# HeadSensors.net
KiCad netlist of a schematic drawn in Altium Designer
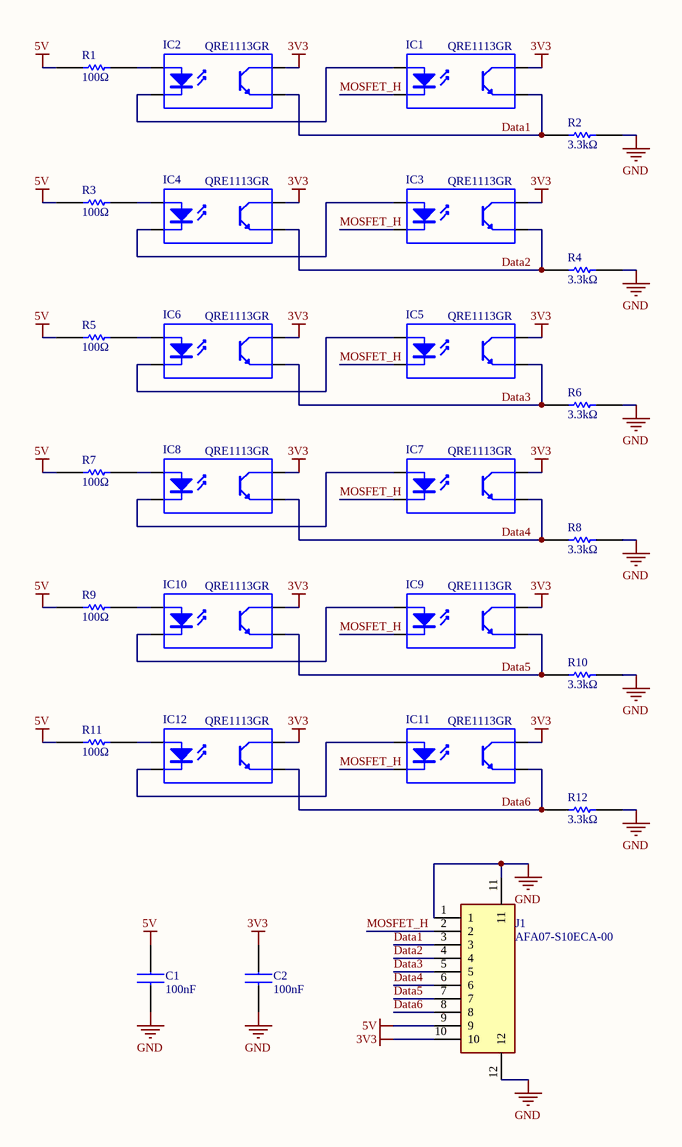
[diagram p0: HeadSensors.SchDoc]

(export (version "E")
  (design (tool "Eeschema 10.0.6"))
  (components
    (comp (ref "C1")
      (value "100nF")
      (footprint "CAP0805")
      (description "Multilayer Ceramic Capacitors MLCC - SMD/SMT 50 V 0.1uF X7R 0805 10%")
      (fields (field (name "MANUFACTURER_PART_NUMBER") "CC0805KRX7R9BB104"))
      (libsource (lib "StandartComponents") (part "CC0805KRX7R9BB104"))
    )
    (comp (ref "C2")
      (value "100nF")
      (footprint "CAP0805")
      (description "Multilayer Ceramic Capacitors MLCC - SMD/SMT 50 V 0.1uF X7R 0805 10%")
      (fields (field (name "MANUFACTURER_PART_NUMBER") "CC0805KRX7R9BB104"))
      (libsource (lib "StandartComponents") (part "CC0805KRX7R9BB104"))
    )
    (comp (ref "IC1")
      (value "QRE1113GR")
      (footprint "SOIC4- Head")
      (description "IC IR-SENSOR")
      (fields
        (field (name "MANUFACTURER") "ON Semiconductor")
        (field (name "LIBRARY CONTROL - PERSON THAT CHECKED FOOTPRINT") "Lucas")
        (field (name "LIBRARY CONTROL - PERSON THAT CHECKED SCHEMATIC") "Lucas")
        (field (name "LIBRARY CONTROL - PERSON THAT DID THE LAST UPDATE FOOTPRINT") "Mateus(Dimas)")
        (field (name "LIBRARY CONTROL - PERSON THAT DID THE LAST UPDATE SCHEMATIC") "Mateus(Dimas)")
      )
      (libsource (lib "MainComponents") (part "QRE1113GR_H"))
    )
    (comp (ref "IC2")
      (value "QRE1113GR")
      (footprint "SOIC4- Head")
      (description "IC IR-SENSOR")
      (fields
        (field (name "MANUFACTURER") "ON Semiconductor")
        (field (name "LIBRARY CONTROL - PERSON THAT CHECKED FOOTPRINT") "Lucas")
        (field (name "LIBRARY CONTROL - PERSON THAT CHECKED SCHEMATIC") "Lucas")
        (field (name "LIBRARY CONTROL - PERSON THAT DID THE LAST UPDATE FOOTPRINT") "Mateus(Dimas)")
        (field (name "LIBRARY CONTROL - PERSON THAT DID THE LAST UPDATE SCHEMATIC") "Mateus(Dimas)")
      )
      (libsource (lib "MainComponents") (part "QRE1113GR_H"))
    )
    (comp (ref "IC3")
      (value "QRE1113GR")
      (footprint "SOIC4- Head")
      (description "IC IR-SENSOR")
      (fields
        (field (name "MANUFACTURER") "ON Semiconductor")
        (field (name "LIBRARY CONTROL - PERSON THAT CHECKED FOOTPRINT") "Lucas")
        (field (name "LIBRARY CONTROL - PERSON THAT CHECKED SCHEMATIC") "Lucas")
        (field (name "LIBRARY CONTROL - PERSON THAT DID THE LAST UPDATE FOOTPRINT") "Mateus(Dimas)")
        (field (name "LIBRARY CONTROL - PERSON THAT DID THE LAST UPDATE SCHEMATIC") "Mateus(Dimas)")
      )
      (libsource (lib "MainComponents") (part "QRE1113GR_H"))
    )
    (comp (ref "IC4")
      (value "QRE1113GR")
      (footprint "SOIC4- Head")
      (description "IC IR-SENSOR")
      (fields
        (field (name "MANUFACTURER") "ON Semiconductor")
        (field (name "LIBRARY CONTROL - PERSON THAT CHECKED FOOTPRINT") "Lucas")
        (field (name "LIBRARY CONTROL - PERSON THAT CHECKED SCHEMATIC") "Lucas")
        (field (name "LIBRARY CONTROL - PERSON THAT DID THE LAST UPDATE FOOTPRINT") "Mateus(Dimas)")
        (field (name "LIBRARY CONTROL - PERSON THAT DID THE LAST UPDATE SCHEMATIC") "Mateus(Dimas)")
      )
      (libsource (lib "MainComponents") (part "QRE1113GR_H"))
    )
    (comp (ref "IC5")
      (value "QRE1113GR")
      (footprint "SOIC4- Head")
      (description "IC IR-SENSOR")
      (fields
        (field (name "MANUFACTURER") "ON Semiconductor")
        (field (name "LIBRARY CONTROL - PERSON THAT CHECKED FOOTPRINT") "Lucas")
        (field (name "LIBRARY CONTROL - PERSON THAT CHECKED SCHEMATIC") "Lucas")
        (field (name "LIBRARY CONTROL - PERSON THAT DID THE LAST UPDATE FOOTPRINT") "Mateus(Dimas)")
        (field (name "LIBRARY CONTROL - PERSON THAT DID THE LAST UPDATE SCHEMATIC") "Mateus(Dimas)")
      )
      (libsource (lib "MainComponents") (part "QRE1113GR_H"))
    )
    (comp (ref "IC6")
      (value "QRE1113GR")
      (footprint "SOIC4- Head")
      (description "IC IR-SENSOR")
      (fields
        (field (name "MANUFACTURER") "ON Semiconductor")
        (field (name "LIBRARY CONTROL - PERSON THAT CHECKED FOOTPRINT") "Lucas")
        (field (name "LIBRARY CONTROL - PERSON THAT CHECKED SCHEMATIC") "Lucas")
        (field (name "LIBRARY CONTROL - PERSON THAT DID THE LAST UPDATE FOOTPRINT") "Mateus(Dimas)")
        (field (name "LIBRARY CONTROL - PERSON THAT DID THE LAST UPDATE SCHEMATIC") "Mateus(Dimas)")
      )
      (libsource (lib "MainComponents") (part "QRE1113GR_H"))
    )
    (comp (ref "IC7")
      (value "QRE1113GR")
      (footprint "SOIC4- Head")
      (description "IC IR-SENSOR")
      (fields
        (field (name "MANUFACTURER") "ON Semiconductor")
        (field (name "LIBRARY CONTROL - PERSON THAT CHECKED FOOTPRINT") "Lucas")
        (field (name "LIBRARY CONTROL - PERSON THAT CHECKED SCHEMATIC") "Lucas")
        (field (name "LIBRARY CONTROL - PERSON THAT DID THE LAST UPDATE FOOTPRINT") "Mateus(Dimas)")
        (field (name "LIBRARY CONTROL - PERSON THAT DID THE LAST UPDATE SCHEMATIC") "Mateus(Dimas)")
      )
      (libsource (lib "MainComponents") (part "QRE1113GR_H"))
    )
    (comp (ref "IC8")
      (value "QRE1113GR")
      (footprint "SOIC4- Head")
      (description "IC IR-SENSOR")
      (fields
        (field (name "MANUFACTURER") "ON Semiconductor")
        (field (name "LIBRARY CONTROL - PERSON THAT CHECKED FOOTPRINT") "Lucas")
        (field (name "LIBRARY CONTROL - PERSON THAT CHECKED SCHEMATIC") "Lucas")
        (field (name "LIBRARY CONTROL - PERSON THAT DID THE LAST UPDATE FOOTPRINT") "Mateus(Dimas)")
        (field (name "LIBRARY CONTROL - PERSON THAT DID THE LAST UPDATE SCHEMATIC") "Mateus(Dimas)")
      )
      (libsource (lib "MainComponents") (part "QRE1113GR_H"))
    )
    (comp (ref "IC9")
      (value "QRE1113GR")
      (footprint "SOIC4- Head")
      (description "IC IR-SENSOR")
      (fields
        (field (name "MANUFACTURER") "ON Semiconductor")
        (field (name "LIBRARY CONTROL - PERSON THAT CHECKED FOOTPRINT") "Lucas")
        (field (name "LIBRARY CONTROL - PERSON THAT CHECKED SCHEMATIC") "Lucas")
        (field (name "LIBRARY CONTROL - PERSON THAT DID THE LAST UPDATE FOOTPRINT") "Mateus(Dimas)")
        (field (name "LIBRARY CONTROL - PERSON THAT DID THE LAST UPDATE SCHEMATIC") "Mateus(Dimas)")
      )
      (libsource (lib "MainComponents") (part "QRE1113GR_H"))
    )
    (comp (ref "IC10")
      (value "QRE1113GR")
      (footprint "SOIC4- Head")
      (description "IC IR-SENSOR")
      (fields
        (field (name "MANUFACTURER") "ON Semiconductor")
        (field (name "LIBRARY CONTROL - PERSON THAT CHECKED FOOTPRINT") "Lucas")
        (field (name "LIBRARY CONTROL - PERSON THAT CHECKED SCHEMATIC") "Lucas")
        (field (name "LIBRARY CONTROL - PERSON THAT DID THE LAST UPDATE FOOTPRINT") "Mateus(Dimas)")
        (field (name "LIBRARY CONTROL - PERSON THAT DID THE LAST UPDATE SCHEMATIC") "Mateus(Dimas)")
      )
      (libsource (lib "MainComponents") (part "QRE1113GR_H"))
    )
    (comp (ref "IC11")
      (value "QRE1113GR")
      (footprint "SOIC4- Head")
      (description "IC IR-SENSOR")
      (fields
        (field (name "MANUFACTURER") "ON Semiconductor")
        (field (name "LIBRARY CONTROL - PERSON THAT CHECKED FOOTPRINT") "Lucas")
        (field (name "LIBRARY CONTROL - PERSON THAT CHECKED SCHEMATIC") "Lucas")
        (field (name "LIBRARY CONTROL - PERSON THAT DID THE LAST UPDATE FOOTPRINT") "Mateus(Dimas)")
        (field (name "LIBRARY CONTROL - PERSON THAT DID THE LAST UPDATE SCHEMATIC") "Mateus(Dimas)")
      )
      (libsource (lib "MainComponents") (part "QRE1113GR_H"))
    )
    (comp (ref "IC12")
      (value "QRE1113GR")
      (footprint "SOIC4- Head")
      (description "IC IR-SENSOR")
      (fields
        (field (name "MANUFACTURER") "ON Semiconductor")
        (field (name "LIBRARY CONTROL - PERSON THAT CHECKED FOOTPRINT") "Lucas")
        (field (name "LIBRARY CONTROL - PERSON THAT CHECKED SCHEMATIC") "Lucas")
        (field (name "LIBRARY CONTROL - PERSON THAT DID THE LAST UPDATE FOOTPRINT") "Mateus(Dimas)")
        (field (name "LIBRARY CONTROL - PERSON THAT DID THE LAST UPDATE SCHEMATIC") "Mateus(Dimas)")
      )
      (libsource (lib "MainComponents") (part "QRE1113GR_H"))
    )
    (comp (ref "J1")
      (value "AFA07-S10ECA-00")
      (footprint "FPC-SMD-P1.00-10P_LCS-SJ-H2.5")
      (libsource (lib "StandartComponents") (part "AFA07-S10ECA-00"))
    )
    (comp (ref "R1")
      (value "100Ω")
      (footprint "RES0805")
      (description "125mW Thick Film Resistors 150V ±100ppm/℃ ±1% 100Ω 0805 Chip Resistor - Surface Mount ROHS")
      (fields (field (name "MANUFACTURER_PART_NUMBER") "0805W8F1000T5E"))
      (libsource (lib "StandartComponents") (part "0805W8F1000T5E"))
    )
    (comp (ref "R2")
      (value "3.3kΩ")
      (footprint "RES0805")
      (description "125mW Thick Film Resistors 150V ±100ppm/℃ ±1% 3.3kΩ 0805 Chip Resistor - Surface Mount ROHS")
      (fields (field (name "MANUFACTURER_PART_NUMBER") "0805W8F3301T5E"))
      (libsource (lib "StandartComponents") (part "0805W8F3301T5E"))
    )
    (comp (ref "R3")
      (value "100Ω")
      (footprint "RES0805")
      (description "125mW Thick Film Resistors 150V ±100ppm/℃ ±1% 100Ω 0805 Chip Resistor - Surface Mount ROHS")
      (fields (field (name "MANUFACTURER_PART_NUMBER") "0805W8F1000T5E"))
      (libsource (lib "StandartComponents") (part "0805W8F1000T5E"))
    )
    (comp (ref "R4")
      (value "3.3kΩ")
      (footprint "RES0805")
      (description "125mW Thick Film Resistors 150V ±100ppm/℃ ±1% 3.3kΩ 0805 Chip Resistor - Surface Mount ROHS")
      (fields (field (name "MANUFACTURER_PART_NUMBER") "0805W8F3301T5E"))
      (libsource (lib "StandartComponents") (part "0805W8F3301T5E"))
    )
    (comp (ref "R5")
      (value "100Ω")
      (footprint "RES0805")
      (description "125mW Thick Film Resistors 150V ±100ppm/℃ ±1% 100Ω 0805 Chip Resistor - Surface Mount ROHS")
      (fields (field (name "MANUFACTURER_PART_NUMBER") "0805W8F1000T5E"))
      (libsource (lib "StandartComponents") (part "0805W8F1000T5E"))
    )
    (comp (ref "R6")
      (value "3.3kΩ")
      (footprint "RES0805")
      (description "125mW Thick Film Resistors 150V ±100ppm/℃ ±1% 3.3kΩ 0805 Chip Resistor - Surface Mount ROHS")
      (fields (field (name "MANUFACTURER_PART_NUMBER") "0805W8F3301T5E"))
      (libsource (lib "StandartComponents") (part "0805W8F3301T5E"))
    )
    (comp (ref "R7")
      (value "100Ω")
      (footprint "RES0805")
      (description "125mW Thick Film Resistors 150V ±100ppm/℃ ±1% 100Ω 0805 Chip Resistor - Surface Mount ROHS")
      (fields (field (name "MANUFACTURER_PART_NUMBER") "0805W8F1000T5E"))
      (libsource (lib "StandartComponents") (part "0805W8F1000T5E"))
    )
    (comp (ref "R8")
      (value "3.3kΩ")
      (footprint "RES0805")
      (description "125mW Thick Film Resistors 150V ±100ppm/℃ ±1% 3.3kΩ 0805 Chip Resistor - Surface Mount ROHS")
      (fields (field (name "MANUFACTURER_PART_NUMBER") "0805W8F3301T5E"))
      (libsource (lib "StandartComponents") (part "0805W8F3301T5E"))
    )
    (comp (ref "R9")
      (value "100Ω")
      (footprint "RES0805")
      (description "125mW Thick Film Resistors 150V ±100ppm/℃ ±1% 100Ω 0805 Chip Resistor - Surface Mount ROHS")
      (fields (field (name "MANUFACTURER_PART_NUMBER") "0805W8F1000T5E"))
      (libsource (lib "StandartComponents") (part "0805W8F1000T5E"))
    )
    (comp (ref "R10")
      (value "3.3kΩ")
      (footprint "RES0805")
      (description "125mW Thick Film Resistors 150V ±100ppm/℃ ±1% 3.3kΩ 0805 Chip Resistor - Surface Mount ROHS")
      (fields (field (name "MANUFACTURER_PART_NUMBER") "0805W8F3301T5E"))
      (libsource (lib "StandartComponents") (part "0805W8F3301T5E"))
    )
    (comp (ref "R11")
      (value "100Ω")
      (footprint "RES0805")
      (description "125mW Thick Film Resistors 150V ±100ppm/℃ ±1% 100Ω 0805 Chip Resistor - Surface Mount ROHS")
      (fields (field (name "MANUFACTURER_PART_NUMBER") "0805W8F1000T5E"))
      (libsource (lib "StandartComponents") (part "0805W8F1000T5E"))
    )
    (comp (ref "R12")
      (value "3.3kΩ")
      (footprint "RES0805")
      (description "125mW Thick Film Resistors 150V ±100ppm/℃ ±1% 3.3kΩ 0805 Chip Resistor - Surface Mount ROHS")
      (fields (field (name "MANUFACTURER_PART_NUMBER") "0805W8F3301T5E"))
      (libsource (lib "StandartComponents") (part "0805W8F3301T5E"))
    )
  )
  (nets
    (net (code "1") (name "/Data1") (class "Default")
      (node (ref "IC1") (pin "4") (pinfunction "E_4") (pintype "passive"))
      (node (ref "IC2") (pin "4") (pinfunction "E_4") (pintype "passive"))
      (node (ref "J1") (pin "3") (pinfunction "3_3") (pintype "passive"))
      (node (ref "R2") (pin "1") (pinfunction "1_1") (pintype "passive"))
    )
    (net (code "2") (name "/Data2") (class "Default")
      (node (ref "IC3") (pin "4") (pinfunction "E_4") (pintype "passive"))
      (node (ref "IC4") (pin "4") (pinfunction "E_4") (pintype "passive"))
      (node (ref "J1") (pin "4") (pinfunction "4_4") (pintype "passive"))
      (node (ref "R4") (pin "1") (pinfunction "1_1") (pintype "passive"))
    )
    (net (code "3") (name "/Data3") (class "Default")
      (node (ref "IC5") (pin "4") (pinfunction "E_4") (pintype "passive"))
      (node (ref "IC6") (pin "4") (pinfunction "E_4") (pintype "passive"))
      (node (ref "J1") (pin "5") (pinfunction "5_5") (pintype "passive"))
      (node (ref "R6") (pin "1") (pinfunction "1_1") (pintype "passive"))
    )
    (net (code "4") (name "/Data4") (class "Default")
      (node (ref "IC7") (pin "4") (pinfunction "E_4") (pintype "passive"))
      (node (ref "IC8") (pin "4") (pinfunction "E_4") (pintype "passive"))
      (node (ref "J1") (pin "6") (pinfunction "6_6") (pintype "passive"))
      (node (ref "R8") (pin "1") (pinfunction "1_1") (pintype "passive"))
    )
    (net (code "5") (name "/Data5") (class "Default")
      (node (ref "IC10") (pin "4") (pinfunction "E_4") (pintype "passive"))
      (node (ref "IC9") (pin "4") (pinfunction "E_4") (pintype "passive"))
      (node (ref "J1") (pin "7") (pinfunction "7_7") (pintype "passive"))
      (node (ref "R10") (pin "1") (pinfunction "1_1") (pintype "passive"))
    )
    (net (code "6") (name "/Data6") (class "Default")
      (node (ref "IC11") (pin "4") (pinfunction "E_4") (pintype "passive"))
      (node (ref "IC12") (pin "4") (pinfunction "E_4") (pintype "passive"))
      (node (ref "J1") (pin "8") (pinfunction "8_8") (pintype "passive"))
      (node (ref "R12") (pin "1") (pinfunction "1_1") (pintype "passive"))
    )
    (net (code "7") (name "/MOSFET_H") (class "Default")
      (node (ref "IC1") (pin "2") (pinfunction "K_2") (pintype "passive"))
      (node (ref "IC11") (pin "2") (pinfunction "K_2") (pintype "passive"))
      (node (ref "IC3") (pin "2") (pinfunction "K_2") (pintype "passive"))
      (node (ref "IC5") (pin "2") (pinfunction "K_2") (pintype "passive"))
      (node (ref "IC7") (pin "2") (pinfunction "K_2") (pintype "passive"))
      (node (ref "IC9") (pin "2") (pinfunction "K_2") (pintype "passive"))
      (node (ref "J1") (pin "2") (pinfunction "2_2") (pintype "passive"))
    )
    (net (code "8") (name "3V3") (class "Default")
      (node (ref "C2") (pin "1") (pinfunction "1_1") (pintype "passive"))
      (node (ref "IC1") (pin "3") (pinfunction "C_3") (pintype "passive"))
      (node (ref "IC10") (pin "3") (pinfunction "C_3") (pintype "passive"))
      (node (ref "IC11") (pin "3") (pinfunction "C_3") (pintype "passive"))
      (node (ref "IC12") (pin "3") (pinfunction "C_3") (pintype "passive"))
      (node (ref "IC2") (pin "3") (pinfunction "C_3") (pintype "passive"))
      (node (ref "IC3") (pin "3") (pinfunction "C_3") (pintype "passive"))
      (node (ref "IC4") (pin "3") (pinfunction "C_3") (pintype "passive"))
      (node (ref "IC5") (pin "3") (pinfunction "C_3") (pintype "passive"))
      (node (ref "IC6") (pin "3") (pinfunction "C_3") (pintype "passive"))
      (node (ref "IC7") (pin "3") (pinfunction "C_3") (pintype "passive"))
      (node (ref "IC8") (pin "3") (pinfunction "C_3") (pintype "passive"))
      (node (ref "IC9") (pin "3") (pinfunction "C_3") (pintype "passive"))
      (node (ref "J1") (pin "10") (pinfunction "10_10") (pintype "passive"))
    )
    (net (code "9") (name "5V") (class "Default")
      (node (ref "C1") (pin "1") (pinfunction "1_1") (pintype "passive"))
      (node (ref "J1") (pin "9") (pinfunction "9_9") (pintype "passive"))
      (node (ref "R1") (pin "1") (pinfunction "1_1") (pintype "passive"))
      (node (ref "R11") (pin "1") (pinfunction "1_1") (pintype "passive"))
      (node (ref "R3") (pin "1") (pinfunction "1_1") (pintype "passive"))
      (node (ref "R5") (pin "1") (pinfunction "1_1") (pintype "passive"))
      (node (ref "R7") (pin "1") (pinfunction "1_1") (pintype "passive"))
      (node (ref "R9") (pin "1") (pinfunction "1_1") (pintype "passive"))
    )
    (net (code "10") (name "GND") (class "Default")
      (node (ref "C1") (pin "2") (pinfunction "2_2") (pintype "passive"))
      (node (ref "C2") (pin "2") (pinfunction "2_2") (pintype "passive"))
      (node (ref "J1") (pin "1") (pinfunction "1_1") (pintype "passive"))
      (node (ref "J1") (pin "11") (pinfunction "11_11") (pintype "passive"))
      (node (ref "J1") (pin "12") (pinfunction "12_12") (pintype "passive"))
      (node (ref "R10") (pin "2") (pinfunction "2_2") (pintype "passive"))
      (node (ref "R12") (pin "2") (pinfunction "2_2") (pintype "passive"))
      (node (ref "R2") (pin "2") (pinfunction "2_2") (pintype "passive"))
      (node (ref "R4") (pin "2") (pinfunction "2_2") (pintype "passive"))
      (node (ref "R6") (pin "2") (pinfunction "2_2") (pintype "passive"))
      (node (ref "R8") (pin "2") (pinfunction "2_2") (pintype "passive"))
    )
    (net (code "11") (name "Net-(IC1-A)") (class "Default")
      (node (ref "IC1") (pin "1") (pinfunction "A_1") (pintype "passive"))
      (node (ref "IC2") (pin "2") (pinfunction "K_2") (pintype "passive"))
    )
    (net (code "12") (name "Net-(IC2-A)") (class "Default")
      (node (ref "IC2") (pin "1") (pinfunction "A_1") (pintype "passive"))
      (node (ref "R1") (pin "2") (pinfunction "2_2") (pintype "passive"))
    )
    (net (code "13") (name "Net-(IC3-A)") (class "Default")
      (node (ref "IC3") (pin "1") (pinfunction "A_1") (pintype "passive"))
      (node (ref "IC4") (pin "2") (pinfunction "K_2") (pintype "passive"))
    )
    (net (code "14") (name "Net-(IC4-A)") (class "Default")
      (node (ref "IC4") (pin "1") (pinfunction "A_1") (pintype "passive"))
      (node (ref "R3") (pin "2") (pinfunction "2_2") (pintype "passive"))
    )
    (net (code "15") (name "Net-(IC5-A)") (class "Default")
      (node (ref "IC5") (pin "1") (pinfunction "A_1") (pintype "passive"))
      (node (ref "IC6") (pin "2") (pinfunction "K_2") (pintype "passive"))
    )
    (net (code "16") (name "Net-(IC6-A)") (class "Default")
      (node (ref "IC6") (pin "1") (pinfunction "A_1") (pintype "passive"))
      (node (ref "R5") (pin "2") (pinfunction "2_2") (pintype "passive"))
    )
    (net (code "17") (name "Net-(IC7-A)") (class "Default")
      (node (ref "IC7") (pin "1") (pinfunction "A_1") (pintype "passive"))
      (node (ref "IC8") (pin "2") (pinfunction "K_2") (pintype "passive"))
    )
    (net (code "18") (name "Net-(IC8-A)") (class "Default")
      (node (ref "IC8") (pin "1") (pinfunction "A_1") (pintype "passive"))
      (node (ref "R7") (pin "2") (pinfunction "2_2") (pintype "passive"))
    )
    (net (code "19") (name "Net-(IC10-A)") (class "Default")
      (node (ref "IC10") (pin "1") (pinfunction "A_1") (pintype "passive"))
      (node (ref "R9") (pin "2") (pinfunction "2_2") (pintype "passive"))
    )
    (net (code "20") (name "Net-(IC10-K)") (class "Default")
      (node (ref "IC10") (pin "2") (pinfunction "K_2") (pintype "passive"))
      (node (ref "IC9") (pin "1") (pinfunction "A_1") (pintype "passive"))
    )
    (net (code "21") (name "Net-(IC11-A)") (class "Default")
      (node (ref "IC11") (pin "1") (pinfunction "A_1") (pintype "passive"))
      (node (ref "IC12") (pin "2") (pinfunction "K_2") (pintype "passive"))
    )
    (net (code "22") (name "Net-(IC12-A)") (class "Default")
      (node (ref "IC12") (pin "1") (pinfunction "A_1") (pintype "passive"))
      (node (ref "R11") (pin "2") (pinfunction "2_2") (pintype "passive"))
    )
  )
)
